# Linefollower_ArduinoNano.net
KiCad netlist of a schematic drawn in EAGLE
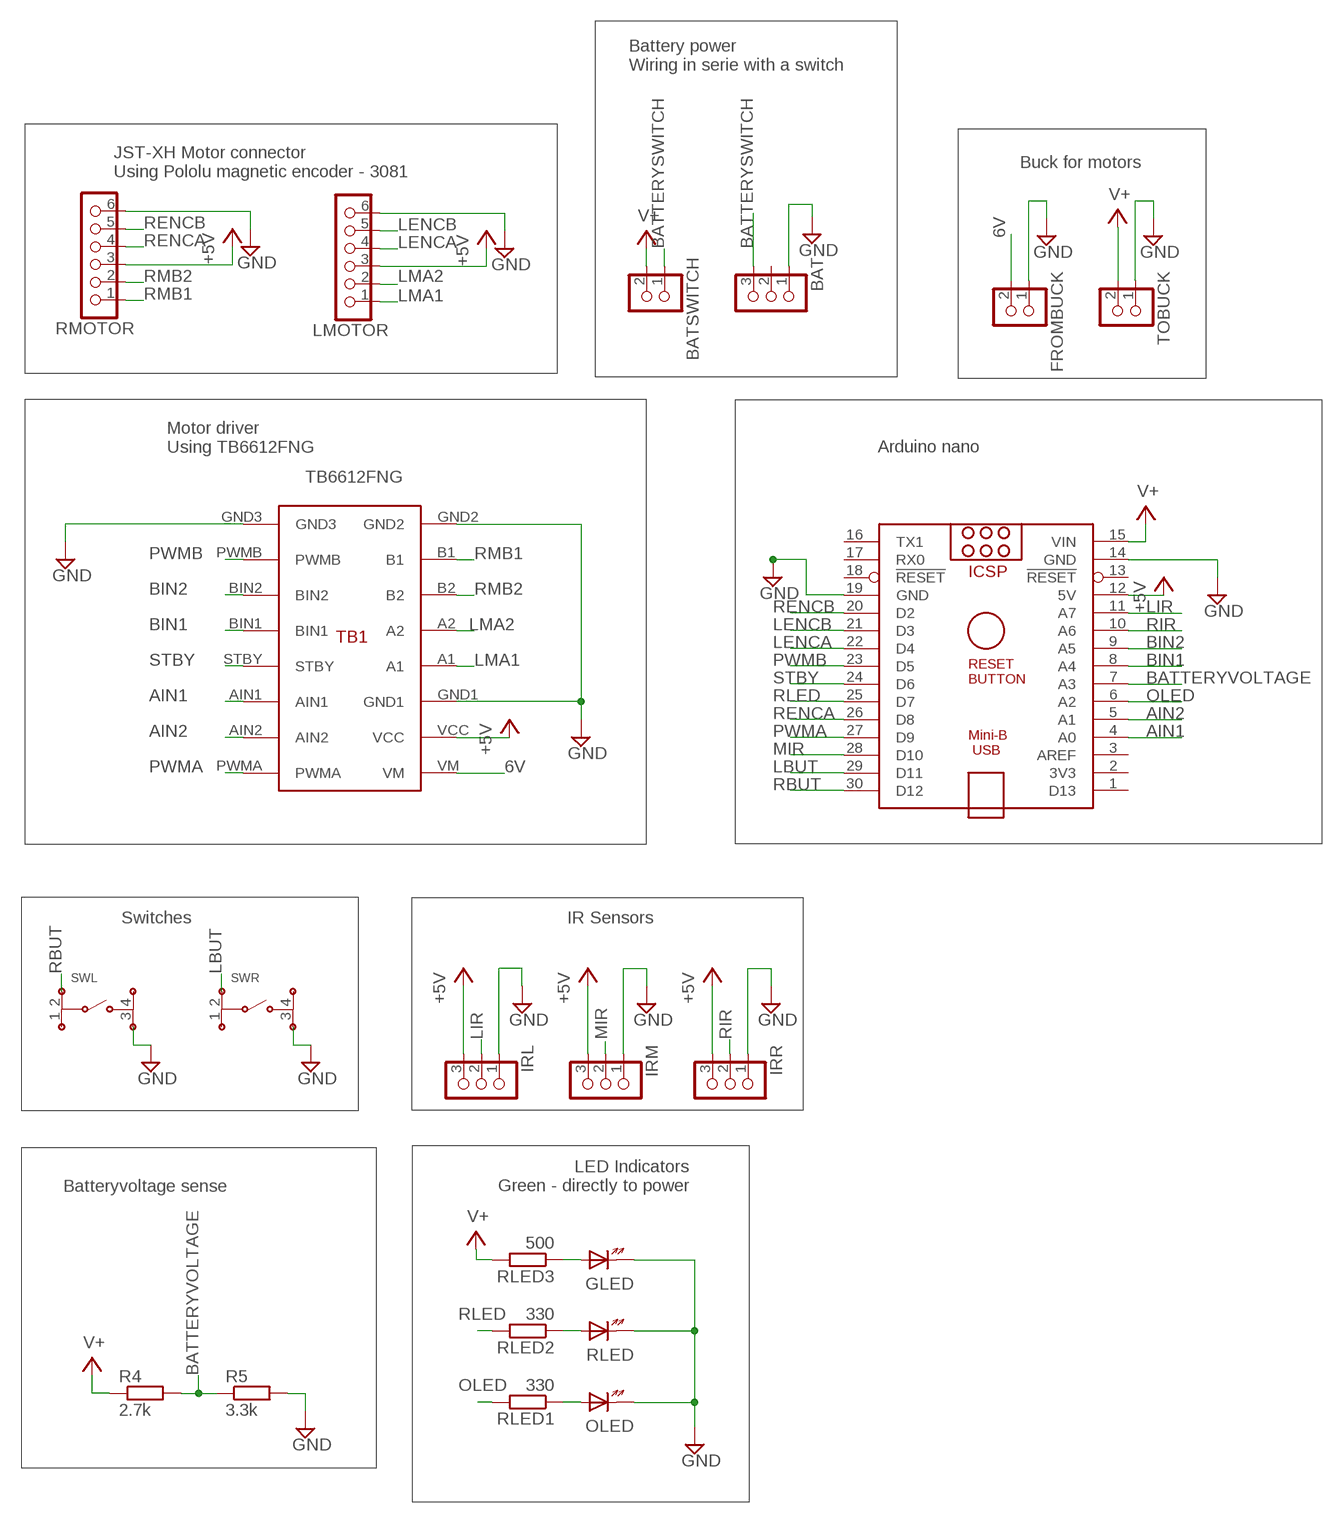
[diagram p0: schematic, sheet 1]

(export (version "E")
  (design (tool "Eeschema 10.0.6"))
  (components
    (comp (ref "ARDUINO_NANO1")
      (value "ARDUINO_NANO")
      (footprint "eagle-import:ARDUINO_NANO")
      (libsource (lib "eagle-import") (part "ARDUINO_NANO"))
    )
    (comp (ref "BAT")
      (value "EH_B3B-EH")
      (footprint "eagle-import:B3B-EH")
      (libsource (lib "eagle-import") (part "EH_B3B-EH"))
    )
    (comp (ref "BATSWITCH")
      (value "EH_B2B-EH")
      (footprint "eagle-import:B2B-EH")
      (libsource (lib "eagle-import") (part "EH_B2B-EH"))
    )
    (comp (ref "FROMBUCK")
      (value "EH_B2B-EH")
      (footprint "eagle-import:B2B-EH")
      (libsource (lib "eagle-import") (part "EH_B2B-EH"))
    )
    (comp (ref "GLED")
      (value "LED5MM")
      (footprint "eagle-import:LED5MM")
      (libsource (lib "eagle-import") (part "LED5MM"))
    )
    (comp (ref "IRL")
      (value "EH_B3B-EH")
      (footprint "eagle-import:B3B-EH")
      (libsource (lib "eagle-import") (part "EH_B3B-EH"))
    )
    (comp (ref "IRM")
      (value "EH_B3B-EH")
      (footprint "eagle-import:B3B-EH")
      (libsource (lib "eagle-import") (part "EH_B3B-EH"))
    )
    (comp (ref "IRR")
      (value "EH_B3B-EH")
      (footprint "eagle-import:B3B-EH")
      (libsource (lib "eagle-import") (part "EH_B3B-EH"))
    )
    (comp (ref "LMOTOR")
      (value "EH_B6B-EH")
      (footprint "eagle-import:B6B-EH")
      (libsource (lib "eagle-import") (part "EH_B6B-EH"))
    )
    (comp (ref "OLED")
      (value "LED5MM")
      (footprint "eagle-import:LED5MM")
      (libsource (lib "eagle-import") (part "LED5MM"))
    )
    (comp (ref "R4")
      (value "2.7k")
      (footprint "eagle-import:R0603")
      (libsource (lib "eagle-import") (part "R0603"))
    )
    (comp (ref "R5")
      (value "3.3k")
      (footprint "eagle-import:R0603")
      (libsource (lib "eagle-import") (part "R0603"))
    )
    (comp (ref "RLED")
      (value "LED5MM")
      (footprint "eagle-import:LED5MM")
      (libsource (lib "eagle-import") (part "LED5MM"))
    )
    (comp (ref "RLED1")
      (value "330")
      (footprint "eagle-import:R0603")
      (libsource (lib "eagle-import") (part "R0603"))
    )
    (comp (ref "RLED2")
      (value "330")
      (footprint "eagle-import:R0603")
      (libsource (lib "eagle-import") (part "R0603"))
    )
    (comp (ref "RLED3")
      (value "500")
      (footprint "eagle-import:R0603")
      (libsource (lib "eagle-import") (part "R0603"))
    )
    (comp (ref "RMOTOR")
      (value "EH_B6B-EH")
      (footprint "eagle-import:B6B-EH")
      (libsource (lib "eagle-import") (part "EH_B6B-EH"))
    )
    (comp (ref "SWL")
      (value "SKHHA/D")
      (footprint "eagle-import:SKHHA_D")
      (libsource (lib "eagle-import") (part "SKHHA/D"))
    )
    (comp (ref "SWR")
      (value "SKHHA/D")
      (footprint "eagle-import:SKHHA_D")
      (libsource (lib "eagle-import") (part "SKHHA/D"))
    )
    (comp (ref "TB1")
      (value "TB6612FNG")
      (footprint "eagle-import:TB6612FNG")
      (libsource (lib "eagle-import") (part "TB6612FNG"))
    )
    (comp (ref "TOBUCK")
      (value "EH_B2B-EH")
      (footprint "eagle-import:B2B-EH")
      (libsource (lib "eagle-import") (part "EH_B2B-EH"))
    )
  )
  (nets
    (net (code "1") (name "+5V") (class "Default")
      (node (ref "ARDUINO_NANO1") (pin "12") (pinfunction "5V_12") (pintype "power_in"))
      (node (ref "IRL") (pin "3") (pinfunction "3_3") (pintype "passive"))
      (node (ref "IRM") (pin "3") (pinfunction "3_3") (pintype "passive"))
      (node (ref "IRR") (pin "3") (pinfunction "3_3") (pintype "passive"))
      (node (ref "LMOTOR") (pin "3") (pinfunction "3_3") (pintype "passive"))
      (node (ref "RMOTOR") (pin "3") (pinfunction "3_3") (pintype "passive"))
      (node (ref "TB1") (pin "VCC") (pinfunction "VCC_VCC") (pintype "bidirectional"))
    )
    (net (code "2") (name "/6V") (class "Default")
      (node (ref "FROMBUCK") (pin "2") (pinfunction "2_2") (pintype "passive"))
      (node (ref "TB1") (pin "VM") (pinfunction "VM_VM") (pintype "bidirectional"))
    )
    (net (code "3") (name "/AIN1") (class "Default")
      (node (ref "ARDUINO_NANO1") (pin "4") (pinfunction "A0_4") (pintype "bidirectional"))
      (node (ref "TB1") (pin "AIN1") (pinfunction "AIN1_AIN1") (pintype "bidirectional"))
    )
    (net (code "4") (name "/AIN2") (class "Default")
      (node (ref "ARDUINO_NANO1") (pin "5") (pinfunction "A1_5") (pintype "bidirectional"))
      (node (ref "TB1") (pin "AIN2") (pinfunction "AIN2_AIN2") (pintype "bidirectional"))
    )
    (net (code "5") (name "/BATTERYSWITCH") (class "Default")
      (node (ref "BAT") (pin "3") (pinfunction "3_3") (pintype "passive"))
      (node (ref "BATSWITCH") (pin "1") (pinfunction "1_1") (pintype "passive"))
    )
    (net (code "6") (name "/BATTERYVOLTAGE") (class "Default")
      (node (ref "ARDUINO_NANO1") (pin "7") (pinfunction "A3_7") (pintype "bidirectional"))
      (node (ref "R4") (pin "2") (pinfunction "2_2") (pintype "passive"))
      (node (ref "R5") (pin "1") (pinfunction "1_1") (pintype "passive"))
    )
    (net (code "7") (name "/BIN1") (class "Default")
      (node (ref "ARDUINO_NANO1") (pin "8") (pinfunction "A4_8") (pintype "bidirectional"))
      (node (ref "TB1") (pin "BIN1") (pinfunction "BIN1_BIN1") (pintype "bidirectional"))
    )
    (net (code "8") (name "/BIN2") (class "Default")
      (node (ref "ARDUINO_NANO1") (pin "9") (pinfunction "A5_9") (pintype "bidirectional"))
      (node (ref "TB1") (pin "BIN2") (pinfunction "BIN2_BIN2") (pintype "bidirectional"))
    )
    (net (code "9") (name "/LBUT") (class "Default")
      (node (ref "ARDUINO_NANO1") (pin "29") (pinfunction "D11_29") (pintype "bidirectional"))
      (node (ref "SWR") (pin "2") (pinfunction "2_2") (pintype "bidirectional"))
    )
    (net (code "10") (name "/LENCA") (class "Default")
      (node (ref "ARDUINO_NANO1") (pin "22") (pinfunction "D4_22") (pintype "bidirectional"))
      (node (ref "LMOTOR") (pin "4") (pinfunction "4_4") (pintype "passive"))
    )
    (net (code "11") (name "/LENCB") (class "Default")
      (node (ref "ARDUINO_NANO1") (pin "21") (pinfunction "D3_21") (pintype "bidirectional"))
      (node (ref "LMOTOR") (pin "5") (pinfunction "5_5") (pintype "passive"))
    )
    (net (code "12") (name "/LIR") (class "Default")
      (node (ref "ARDUINO_NANO1") (pin "11") (pinfunction "A7_11") (pintype "bidirectional"))
      (node (ref "IRL") (pin "2") (pinfunction "2_2") (pintype "passive"))
    )
    (net (code "13") (name "/LMA1") (class "Default")
      (node (ref "LMOTOR") (pin "1") (pinfunction "1_1") (pintype "passive"))
      (node (ref "TB1") (pin "A1") (pinfunction "A1_A1") (pintype "bidirectional"))
    )
    (net (code "14") (name "/LMA2") (class "Default")
      (node (ref "LMOTOR") (pin "2") (pinfunction "2_2") (pintype "passive"))
      (node (ref "TB1") (pin "A2") (pinfunction "A2_A2") (pintype "bidirectional"))
    )
    (net (code "15") (name "/MIR") (class "Default")
      (node (ref "ARDUINO_NANO1") (pin "28") (pinfunction "D10_28") (pintype "bidirectional"))
      (node (ref "IRM") (pin "2") (pinfunction "2_2") (pintype "passive"))
    )
    (net (code "16") (name "/OLED") (class "Default")
      (node (ref "ARDUINO_NANO1") (pin "6") (pinfunction "A2_6") (pintype "bidirectional"))
      (node (ref "RLED1") (pin "2") (pinfunction "2_2") (pintype "passive"))
    )
    (net (code "17") (name "/PWMA") (class "Default")
      (node (ref "ARDUINO_NANO1") (pin "27") (pinfunction "D9_27") (pintype "bidirectional"))
      (node (ref "TB1") (pin "PWMA") (pinfunction "PWMA_PWMA") (pintype "bidirectional"))
    )
    (net (code "18") (name "/PWMB") (class "Default")
      (node (ref "ARDUINO_NANO1") (pin "23") (pinfunction "D5_23") (pintype "bidirectional"))
      (node (ref "TB1") (pin "PWMB") (pinfunction "PWMB_PWMB") (pintype "bidirectional"))
    )
    (net (code "19") (name "/RBUT") (class "Default")
      (node (ref "ARDUINO_NANO1") (pin "30") (pinfunction "D12_30") (pintype "bidirectional"))
      (node (ref "SWL") (pin "2") (pinfunction "2_2") (pintype "bidirectional"))
    )
    (net (code "20") (name "/RENCA") (class "Default")
      (node (ref "ARDUINO_NANO1") (pin "26") (pinfunction "D8_26") (pintype "bidirectional"))
      (node (ref "RMOTOR") (pin "4") (pinfunction "4_4") (pintype "passive"))
    )
    (net (code "21") (name "/RENCB") (class "Default")
      (node (ref "ARDUINO_NANO1") (pin "20") (pinfunction "D2_20") (pintype "bidirectional"))
      (node (ref "RMOTOR") (pin "5") (pinfunction "5_5") (pintype "passive"))
    )
    (net (code "22") (name "/RIR") (class "Default")
      (node (ref "ARDUINO_NANO1") (pin "10") (pinfunction "A6_10") (pintype "bidirectional"))
      (node (ref "IRR") (pin "2") (pinfunction "2_2") (pintype "passive"))
    )
    (net (code "23") (name "/RLED") (class "Default")
      (node (ref "ARDUINO_NANO1") (pin "25") (pinfunction "D7_25") (pintype "bidirectional"))
      (node (ref "RLED2") (pin "2") (pinfunction "2_2") (pintype "passive"))
    )
    (net (code "24") (name "/RMB1") (class "Default")
      (node (ref "RMOTOR") (pin "1") (pinfunction "1_1") (pintype "passive"))
      (node (ref "TB1") (pin "B1") (pinfunction "B1_B1") (pintype "bidirectional"))
    )
    (net (code "25") (name "/RMB2") (class "Default")
      (node (ref "RMOTOR") (pin "2") (pinfunction "2_2") (pintype "passive"))
      (node (ref "TB1") (pin "B2") (pinfunction "B2_B2") (pintype "bidirectional"))
    )
    (net (code "26") (name "/STBY") (class "Default")
      (node (ref "ARDUINO_NANO1") (pin "24") (pinfunction "D6_24") (pintype "bidirectional"))
      (node (ref "TB1") (pin "STBY") (pinfunction "STBY_STBY") (pintype "bidirectional"))
    )
    (net (code "27") (name "GND") (class "Default")
      (node (ref "ARDUINO_NANO1") (pin "14") (pinfunction "GND_14") (pintype "power_in"))
      (node (ref "ARDUINO_NANO1") (pin "19") (pinfunction "GND_19") (pintype "power_in"))
      (node (ref "BAT") (pin "1") (pinfunction "1_1") (pintype "passive"))
      (node (ref "FROMBUCK") (pin "1") (pinfunction "1_1") (pintype "passive"))
      (node (ref "GLED") (pin "K") (pinfunction "K_K") (pintype "passive"))
      (node (ref "IRL") (pin "1") (pinfunction "1_1") (pintype "passive"))
      (node (ref "IRM") (pin "1") (pinfunction "1_1") (pintype "passive"))
      (node (ref "IRR") (pin "1") (pinfunction "1_1") (pintype "passive"))
      (node (ref "LMOTOR") (pin "6") (pinfunction "6_6") (pintype "passive"))
      (node (ref "OLED") (pin "K") (pinfunction "K_K") (pintype "passive"))
      (node (ref "R5") (pin "2") (pinfunction "2_2") (pintype "passive"))
      (node (ref "RLED") (pin "K") (pinfunction "K_K") (pintype "passive"))
      (node (ref "RMOTOR") (pin "6") (pinfunction "6_6") (pintype "passive"))
      (node (ref "SWL") (pin "3") (pinfunction "3_3") (pintype "bidirectional"))
      (node (ref "SWR") (pin "3") (pinfunction "3_3") (pintype "bidirectional"))
      (node (ref "TB1") (pin "GND1") (pinfunction "GND1_GND1") (pintype "bidirectional"))
      (node (ref "TB1") (pin "GND2") (pinfunction "GND2_GND2") (pintype "bidirectional"))
      (node (ref "TB1") (pin "GND3") (pinfunction "GND3_GND3") (pintype "bidirectional"))
      (node (ref "TOBUCK") (pin "1") (pinfunction "1_1") (pintype "passive"))
    )
    (net (code "28") (name "Net-(GLED-PadA)") (class "Default")
      (node (ref "GLED") (pin "A") (pinfunction "A_A") (pintype "passive"))
      (node (ref "RLED3") (pin "1") (pinfunction "1_1") (pintype "passive"))
    )
    (net (code "29") (name "Net-(OLED-PadA)") (class "Default")
      (node (ref "OLED") (pin "A") (pinfunction "A_A") (pintype "passive"))
      (node (ref "RLED1") (pin "1") (pinfunction "1_1") (pintype "passive"))
    )
    (net (code "30") (name "Net-(RLED-PadA)") (class "Default")
      (node (ref "RLED") (pin "A") (pinfunction "A_A") (pintype "passive"))
      (node (ref "RLED2") (pin "1") (pinfunction "1_1") (pintype "passive"))
    )
    (net (code "31") (name "V+") (class "Default")
      (node (ref "ARDUINO_NANO1") (pin "15") (pinfunction "VIN_15") (pintype "power_in"))
      (node (ref "BATSWITCH") (pin "2") (pinfunction "2_2") (pintype "passive"))
      (node (ref "R4") (pin "1") (pinfunction "1_1") (pintype "passive"))
      (node (ref "RLED3") (pin "2") (pinfunction "2_2") (pintype "passive"))
      (node (ref "TOBUCK") (pin "2") (pinfunction "2_2") (pintype "passive"))
    )
    (net (code "32") (name "unconnected-(ARDUINO_NANO1-3V3-Pad2)") (class "Default")
      (node (ref "ARDUINO_NANO1") (pin "2") (pinfunction "3V3_2") (pintype "output"))
    )
    (net (code "33") (name "unconnected-(ARDUINO_NANO1-AREF-Pad3)") (class "Default")
      (node (ref "ARDUINO_NANO1") (pin "3") (pinfunction "AREF_3") (pintype "input"))
    )
    (net (code "34") (name "unconnected-(ARDUINO_NANO1-D13-Pad1)") (class "Default")
      (node (ref "ARDUINO_NANO1") (pin "1") (pinfunction "D13_1") (pintype "bidirectional"))
    )
    (net (code "35") (name "unconnected-(ARDUINO_NANO1-RX0-Pad17)") (class "Default")
      (node (ref "ARDUINO_NANO1") (pin "17") (pinfunction "RX0_17") (pintype "bidirectional"))
    )
    (net (code "36") (name "unconnected-(ARDUINO_NANO1-TX1-Pad16)") (class "Default")
      (node (ref "ARDUINO_NANO1") (pin "16") (pinfunction "TX1_16") (pintype "bidirectional"))
    )
    (net (code "37") (name "unconnected-(ARDUINO_NANO1-~{RESET}-Pad13)") (class "Default")
      (node (ref "ARDUINO_NANO1") (pin "13") (pinfunction "~{RESET}_13") (pintype "input"))
    )
    (net (code "38") (name "unconnected-(ARDUINO_NANO1-~{RESET}-Pad18)") (class "Default")
      (node (ref "ARDUINO_NANO1") (pin "18") (pinfunction "~{RESET}_18") (pintype "input"))
    )
    (net (code "39") (name "unconnected-(BAT-Pad2)") (class "Default")
      (node (ref "BAT") (pin "2") (pinfunction "2_2") (pintype "passive"))
    )
    (net (code "40") (name "unconnected-(SWL-Pad1)") (class "Default")
      (node (ref "SWL") (pin "1") (pinfunction "1_1") (pintype "bidirectional"))
    )
    (net (code "41") (name "unconnected-(SWL-Pad4)") (class "Default")
      (node (ref "SWL") (pin "4") (pinfunction "4_4") (pintype "bidirectional"))
    )
    (net (code "42") (name "unconnected-(SWR-Pad1)") (class "Default")
      (node (ref "SWR") (pin "1") (pinfunction "1_1") (pintype "bidirectional"))
    )
    (net (code "43") (name "unconnected-(SWR-Pad4)") (class "Default")
      (node (ref "SWR") (pin "4") (pinfunction "4_4") (pintype "bidirectional"))
    )
  )
)
